# STM8_IoT_Board.net
KiCad netlist of a schematic drawn in EAGLE
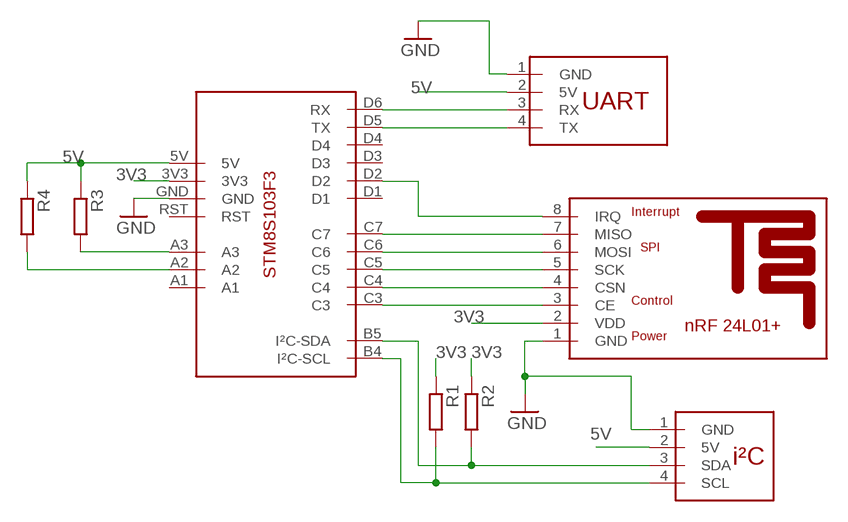
[diagram p0: schematic, sheet 1]

(export (version "E")
  (design (tool "Eeschema 10.0.6"))
  (components
    (comp (ref "R1")
      (value "1k")
      (footprint "eagle-import:R1206")
      (libsource (lib "eagle-import") (part "R-EU_R1206"))
    )
    (comp (ref "R2")
      (value "1k")
      (footprint "eagle-import:R1206")
      (libsource (lib "eagle-import") (part "R-EU_R1206"))
    )
    (comp (ref "R3")
      (value "1k")
      (footprint "eagle-import:R1206")
      (libsource (lib "eagle-import") (part "R-EU_R1206"))
    )
    (comp (ref "R4")
      (value "1k")
      (footprint "eagle-import:R1206")
      (libsource (lib "eagle-import") (part "R-EU_R1206"))
    )
    (comp (ref "U$1")
      (value "STM8S103F3-DEVKITMINI")
      (footprint "eagle-import:STM8S103F3-DEVKIT-MINI")
      (libsource (lib "eagle-import") (part "STM8S103F3-DEVKITMINI"))
    )
    (comp (ref "U$2")
      (value "NRF24L01+REFDESIGNMINI")
      (footprint "eagle-import:NRF24L01+REFDESIGN-MINI")
      (libsource (lib "eagle-import") (part "NRF24L01+REFDESIGNMINI"))
    )
    (comp (ref "U$3")
      (value "UARTMINI")
      (footprint "eagle-import:UART-MINI")
      (libsource (lib "eagle-import") (part "UARTMINI"))
    )
    (comp (ref "U$4")
      (value "I2CMINI")
      (footprint "eagle-import:I2C-MINI")
      (libsource (lib "eagle-import") (part "I2CMINI"))
    )
  )
  (nets
    (net (code "1") (name "/3V3") (class "Default")
      (node (ref "R1") (pin "1") (pinfunction "1_1") (pintype "passive"))
      (node (ref "R2") (pin "1") (pinfunction "1_1") (pintype "passive"))
      (node (ref "U$1") (pin "3V3") (pinfunction "3V3_3V3") (pintype "bidirectional"))
      (node (ref "U$2") (pin "2") (pinfunction "VDD_2") (pintype "bidirectional"))
    )
    (net (code "2") (name "/5V") (class "Default")
      (node (ref "R3") (pin "1") (pinfunction "1_1") (pintype "passive"))
      (node (ref "R4") (pin "1") (pinfunction "1_1") (pintype "passive"))
      (node (ref "U$1") (pin "5V") (pinfunction "5V_5V") (pintype "bidirectional"))
      (node (ref "U$3") (pin "2") (pinfunction "5V_2") (pintype "bidirectional"))
      (node (ref "U$4") (pin "2") (pinfunction "5V_2") (pintype "bidirectional"))
    )
    (net (code "3") (name "GND") (class "Default")
      (node (ref "U$1") (pin "GND") (pinfunction "GND_GND") (pintype "bidirectional"))
      (node (ref "U$2") (pin "1") (pinfunction "GND_1") (pintype "bidirectional"))
      (node (ref "U$3") (pin "1") (pinfunction "GND_1") (pintype "bidirectional"))
      (node (ref "U$4") (pin "1") (pinfunction "GND_1") (pintype "bidirectional"))
    )
    (net (code "4") (name "Net-(R3-Pad2)") (class "Default")
      (node (ref "R3") (pin "2") (pinfunction "2_2") (pintype "passive"))
      (node (ref "U$1") (pin "A3") (pinfunction "A3_A3") (pintype "bidirectional"))
    )
    (net (code "5") (name "Net-(R4-Pad2)") (class "Default")
      (node (ref "R4") (pin "2") (pinfunction "2_2") (pintype "passive"))
      (node (ref "U$1") (pin "A2") (pinfunction "A2_A2") (pintype "bidirectional"))
    )
    (net (code "6") (name "Net-(U$1-I²C-SCL)") (class "Default")
      (node (ref "R1") (pin "2") (pinfunction "2_2") (pintype "passive"))
      (node (ref "U$1") (pin "B4") (pinfunction "I²C-SCL_B4") (pintype "bidirectional"))
      (node (ref "U$4") (pin "4") (pinfunction "SCL_4") (pintype "bidirectional"))
    )
    (net (code "7") (name "Net-(U$1-I²C-SDA)") (class "Default")
      (node (ref "R2") (pin "2") (pinfunction "2_2") (pintype "passive"))
      (node (ref "U$1") (pin "B5") (pinfunction "I²C-SDA_B5") (pintype "bidirectional"))
      (node (ref "U$4") (pin "3") (pinfunction "SDA_3") (pintype "bidirectional"))
    )
    (net (code "8") (name "Net-(U$1-RX)") (class "Default")
      (node (ref "U$1") (pin "D6") (pinfunction "RX_D6") (pintype "bidirectional"))
      (node (ref "U$3") (pin "3") (pinfunction "RX_3") (pintype "bidirectional"))
    )
    (net (code "9") (name "Net-(U$1-TX)") (class "Default")
      (node (ref "U$1") (pin "D5") (pinfunction "TX_D5") (pintype "bidirectional"))
      (node (ref "U$3") (pin "4") (pinfunction "TX_4") (pintype "bidirectional"))
    )
    (net (code "10") (name "Net-(U$2-CE)") (class "Default")
      (node (ref "U$1") (pin "C3") (pinfunction "C3_C3") (pintype "bidirectional"))
      (node (ref "U$2") (pin "3") (pinfunction "CE_3") (pintype "bidirectional"))
    )
    (net (code "11") (name "Net-(U$2-CSN)") (class "Default")
      (node (ref "U$1") (pin "C4") (pinfunction "C4_C4") (pintype "bidirectional"))
      (node (ref "U$2") (pin "4") (pinfunction "CSN_4") (pintype "bidirectional"))
    )
    (net (code "12") (name "Net-(U$2-IRQ)") (class "Default")
      (node (ref "U$1") (pin "D2") (pinfunction "D2_D2") (pintype "bidirectional"))
      (node (ref "U$2") (pin "8") (pinfunction "IRQ_8") (pintype "bidirectional"))
    )
    (net (code "13") (name "Net-(U$2-MISO)") (class "Default")
      (node (ref "U$1") (pin "C7") (pinfunction "C7_C7") (pintype "bidirectional"))
      (node (ref "U$2") (pin "7") (pinfunction "MISO_7") (pintype "bidirectional"))
    )
    (net (code "14") (name "Net-(U$2-MOSI)") (class "Default")
      (node (ref "U$1") (pin "C6") (pinfunction "C6_C6") (pintype "bidirectional"))
      (node (ref "U$2") (pin "6") (pinfunction "MOSI_6") (pintype "bidirectional"))
    )
    (net (code "15") (name "Net-(U$2-SCK)") (class "Default")
      (node (ref "U$1") (pin "C5") (pinfunction "C5_C5") (pintype "bidirectional"))
      (node (ref "U$2") (pin "5") (pinfunction "SCK_5") (pintype "bidirectional"))
    )
    (net (code "16") (name "unconnected-(U$1-PadA1)") (class "Default")
      (node (ref "U$1") (pin "A1") (pinfunction "A1_A1") (pintype "bidirectional"))
    )
    (net (code "17") (name "unconnected-(U$1-PadD1)") (class "Default")
      (node (ref "U$1") (pin "D1") (pinfunction "D1_D1") (pintype "bidirectional"))
    )
    (net (code "18") (name "unconnected-(U$1-PadD3)") (class "Default")
      (node (ref "U$1") (pin "D3") (pinfunction "D3_D3") (pintype "bidirectional"))
    )
    (net (code "19") (name "unconnected-(U$1-PadD4)") (class "Default")
      (node (ref "U$1") (pin "D4") (pinfunction "D4_D4") (pintype "bidirectional"))
    )
    (net (code "20") (name "unconnected-(U$1-PadRST)") (class "Default")
      (node (ref "U$1") (pin "RST") (pinfunction "RST_RST") (pintype "bidirectional"))
    )
  )
)
